# OeShield.net
KiCad netlist of a schematic drawn in EAGLE
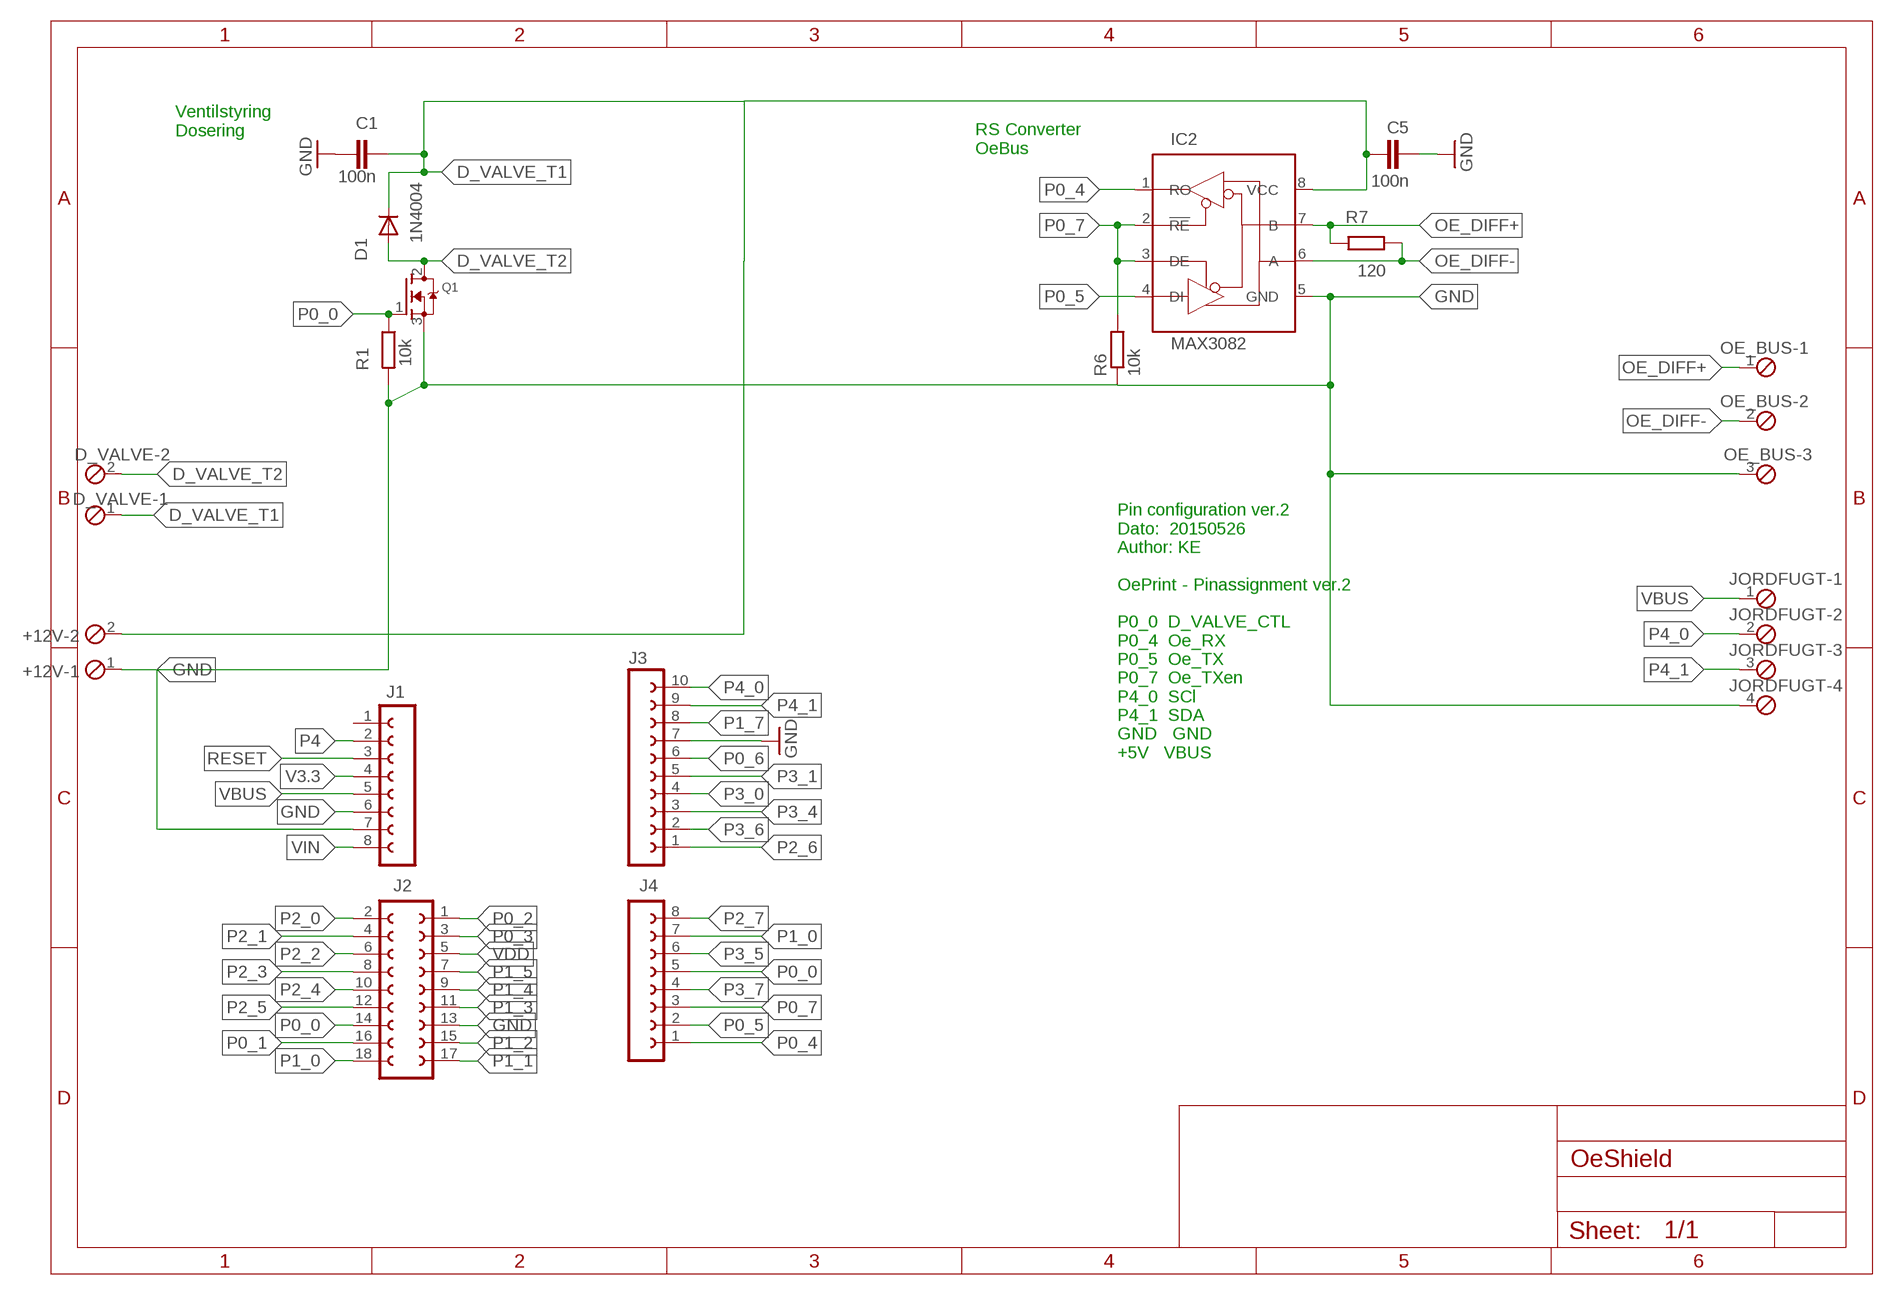
[diagram p0: schematic, sheet 1]

(export (version "E")
  (design (tool "Eeschema 10.0.6"))
  (components
    (comp (ref "+12V")
      (value "MPT2")
      (footprint "eagle-import:2POL254")
      (libsource (lib "eagle-import") (part "MPT2"))
    )
    (comp (ref "C1")
      (value "100n")
      (footprint "eagle-import:C5B3")
      (libsource (lib "eagle-import") (part "C5/3"))
    )
    (comp (ref "C5")
      (value "100n")
      (footprint "eagle-import:C5B3")
      (libsource (lib "eagle-import") (part "C5/3"))
    )
    (comp (ref "D1")
      (value "1N4004")
      (footprint "eagle-import:DO41-10")
      (libsource (lib "eagle-import") (part "1N4004"))
    )
    (comp (ref "D_VALVE")
      (value "MPT2")
      (footprint "eagle-import:2POL254")
      (libsource (lib "eagle-import") (part "MPT2"))
    )
    (comp (ref "IC2")
      (value "MAX3082")
      (footprint "eagle-import:DIL08")
      (libsource (lib "eagle-import") (part "MAX3082CPD"))
    )
    (comp (ref "J1")
      (value "FE08-1")
      (footprint "eagle-import:FE08")
      (libsource (lib "eagle-import") (part "FE08-1"))
    )
    (comp (ref "J2")
      (value "FE09-2")
      (footprint "eagle-import:FE09-2")
      (libsource (lib "eagle-import") (part "FE09-2"))
    )
    (comp (ref "J3")
      (value "FE10-1")
      (footprint "eagle-import:FE10")
      (libsource (lib "eagle-import") (part "FE10-1"))
    )
    (comp (ref "J4")
      (value "FE08-1")
      (footprint "eagle-import:FE08")
      (libsource (lib "eagle-import") (part "FE08-1"))
    )
    (comp (ref "JORDFUGT")
      (value "MPT4")
      (footprint "eagle-import:4POL254")
      (libsource (lib "eagle-import") (part "MPT4"))
    )
    (comp (ref "OE_BUS")
      (value "MPT3")
      (footprint "eagle-import:3POL254")
      (libsource (lib "eagle-import") (part "MPT3"))
    )
    (comp (ref "Q1")
      (value "MOSFET-NGDS_TO220V")
      (footprint "eagle-import:TO220V")
      (libsource (lib "eagle-import") (part "MOSFET-NGDS_TO220V"))
    )
    (comp (ref "R1")
      (value "10k")
      (footprint "eagle-import:0207_12")
      (libsource (lib "eagle-import") (part "R-EU_0207/12"))
    )
    (comp (ref "R6")
      (value "10k")
      (footprint "eagle-import:0207_12")
      (libsource (lib "eagle-import") (part "R-EU_0207/12"))
    )
    (comp (ref "R7")
      (value "120")
      (footprint "eagle-import:0207_12")
      (libsource (lib "eagle-import") (part "R-EU_0207/12"))
    )
  )
  (nets
    (net (code "1") (name "D_VALVE_T1") (class "Default")
      (node (ref "+12V") (pin "2") (pinfunction "1_2") (pintype "passive"))
      (node (ref "C1") (pin "1") (pinfunction "1_1") (pintype "passive"))
      (node (ref "C5") (pin "1") (pinfunction "1_1") (pintype "passive"))
      (node (ref "D1") (pin "C") (pinfunction "C_C") (pintype "passive"))
      (node (ref "D_VALVE") (pin "1") (pinfunction "1_1") (pintype "passive"))
      (node (ref "IC2") (pin "8") (pinfunction "VCC_8") (pintype "output"))
    )
    (net (code "2") (name "D_VALVE_T2") (class "Default")
      (node (ref "D1") (pin "A") (pinfunction "A_A") (pintype "passive"))
      (node (ref "D_VALVE") (pin "2") (pinfunction "1_2") (pintype "passive"))
      (node (ref "Q1") (pin "2") (pinfunction "D_2") (pintype "bidirectional"))
    )
    (net (code "3") (name "GND") (class "Default")
      (node (ref "+12V") (pin "1") (pinfunction "1_1") (pintype "passive"))
      (node (ref "C1") (pin "2") (pinfunction "2_2") (pintype "passive"))
      (node (ref "C5") (pin "2") (pinfunction "2_2") (pintype "passive"))
      (node (ref "IC2") (pin "5") (pinfunction "GND_5") (pintype "input"))
      (node (ref "J1") (pin "6") (pinfunction "6_6") (pintype "passive"))
      (node (ref "J1") (pin "7") (pinfunction "7_7") (pintype "passive"))
      (node (ref "J2") (pin "13") (pinfunction "13_13") (pintype "passive"))
      (node (ref "J3") (pin "7") (pinfunction "7_7") (pintype "passive"))
      (node (ref "JORDFUGT") (pin "4") (pinfunction "1_4") (pintype "passive"))
      (node (ref "OE_BUS") (pin "3") (pinfunction "1_3") (pintype "passive"))
      (node (ref "Q1") (pin "3") (pinfunction "S_3") (pintype "bidirectional"))
      (node (ref "R1") (pin "2") (pinfunction "2_2") (pintype "passive"))
      (node (ref "R6") (pin "1") (pinfunction "1_1") (pintype "passive"))
    )
    (net (code "4") (name "OE_DIFF+") (class "Default")
      (node (ref "IC2") (pin "7") (pinfunction "B_7") (pintype "output"))
      (node (ref "OE_BUS") (pin "1") (pinfunction "1_1") (pintype "passive"))
      (node (ref "R7") (pin "2") (pinfunction "2_2") (pintype "passive"))
    )
    (net (code "5") (name "OE_DIFF-") (class "Default")
      (node (ref "IC2") (pin "6") (pinfunction "A_6") (pintype "input"))
      (node (ref "OE_BUS") (pin "2") (pinfunction "1_2") (pintype "passive"))
      (node (ref "R7") (pin "1") (pinfunction "1_1") (pintype "passive"))
    )
    (net (code "6") (name "P0_0") (class "Default")
      (node (ref "J2") (pin "14") (pinfunction "14_14") (pintype "passive"))
      (node (ref "J4") (pin "5") (pinfunction "5_5") (pintype "passive"))
      (node (ref "Q1") (pin "1") (pinfunction "G_1") (pintype "bidirectional"))
      (node (ref "R1") (pin "1") (pinfunction "1_1") (pintype "passive"))
    )
    (net (code "7") (name "P0_1") (class "Default")
      (node (ref "J2") (pin "16") (pinfunction "16_16") (pintype "passive"))
    )
    (net (code "8") (name "P0_2") (class "Default")
      (node (ref "J2") (pin "1") (pinfunction "1_1") (pintype "passive"))
    )
    (net (code "9") (name "P0_3") (class "Default")
      (node (ref "J2") (pin "3") (pinfunction "3_3") (pintype "passive"))
    )
    (net (code "10") (name "P0_4") (class "Default")
      (node (ref "IC2") (pin "1") (pinfunction "RO_1") (pintype "output"))
      (node (ref "J4") (pin "1") (pinfunction "1_1") (pintype "passive"))
    )
    (net (code "11") (name "P0_5") (class "Default")
      (node (ref "IC2") (pin "4") (pinfunction "DI_4") (pintype "input"))
      (node (ref "J4") (pin "2") (pinfunction "2_2") (pintype "passive"))
    )
    (net (code "12") (name "P0_6") (class "Default")
      (node (ref "J3") (pin "6") (pinfunction "6_6") (pintype "passive"))
    )
    (net (code "13") (name "P0_7") (class "Default")
      (node (ref "IC2") (pin "2") (pinfunction "~{RE}_2") (pintype "input"))
      (node (ref "IC2") (pin "3") (pinfunction "DE_3") (pintype "input"))
      (node (ref "J4") (pin "3") (pinfunction "3_3") (pintype "passive"))
      (node (ref "R6") (pin "2") (pinfunction "2_2") (pintype "passive"))
    )
    (net (code "14") (name "P1_0") (class "Default")
      (node (ref "J2") (pin "18") (pinfunction "18_18") (pintype "passive"))
      (node (ref "J4") (pin "7") (pinfunction "7_7") (pintype "passive"))
    )
    (net (code "15") (name "P1_1") (class "Default")
      (node (ref "J2") (pin "17") (pinfunction "17_17") (pintype "passive"))
    )
    (net (code "16") (name "P1_2") (class "Default")
      (node (ref "J2") (pin "15") (pinfunction "15_15") (pintype "passive"))
    )
    (net (code "17") (name "P1_3") (class "Default")
      (node (ref "J2") (pin "11") (pinfunction "11_11") (pintype "passive"))
    )
    (net (code "18") (name "P1_4") (class "Default")
      (node (ref "J2") (pin "9") (pinfunction "9_9") (pintype "passive"))
    )
    (net (code "19") (name "P1_5") (class "Default")
      (node (ref "J2") (pin "7") (pinfunction "7_7") (pintype "passive"))
    )
    (net (code "20") (name "P1_7") (class "Default")
      (node (ref "J3") (pin "8") (pinfunction "8_8") (pintype "passive"))
    )
    (net (code "21") (name "P2_0") (class "Default")
      (node (ref "J2") (pin "2") (pinfunction "2_2") (pintype "passive"))
    )
    (net (code "22") (name "P2_1") (class "Default")
      (node (ref "J2") (pin "4") (pinfunction "4_4") (pintype "passive"))
    )
    (net (code "23") (name "P2_2") (class "Default")
      (node (ref "J2") (pin "6") (pinfunction "6_6") (pintype "passive"))
    )
    (net (code "24") (name "P2_3") (class "Default")
      (node (ref "J2") (pin "8") (pinfunction "8_8") (pintype "passive"))
    )
    (net (code "25") (name "P2_4") (class "Default")
      (node (ref "J2") (pin "10") (pinfunction "10_10") (pintype "passive"))
    )
    (net (code "26") (name "P2_5") (class "Default")
      (node (ref "J2") (pin "12") (pinfunction "12_12") (pintype "passive"))
    )
    (net (code "27") (name "P2_6") (class "Default")
      (node (ref "J3") (pin "1") (pinfunction "1_1") (pintype "passive"))
    )
    (net (code "28") (name "P2_7") (class "Default")
      (node (ref "J4") (pin "8") (pinfunction "8_8") (pintype "passive"))
    )
    (net (code "29") (name "P3_0") (class "Default")
      (node (ref "J3") (pin "4") (pinfunction "4_4") (pintype "passive"))
    )
    (net (code "30") (name "P3_1") (class "Default")
      (node (ref "J3") (pin "5") (pinfunction "5_5") (pintype "passive"))
    )
    (net (code "31") (name "P3_4") (class "Default")
      (node (ref "J3") (pin "3") (pinfunction "3_3") (pintype "passive"))
    )
    (net (code "32") (name "P3_5") (class "Default")
      (node (ref "J4") (pin "6") (pinfunction "6_6") (pintype "passive"))
    )
    (net (code "33") (name "P3_6") (class "Default")
      (node (ref "J3") (pin "2") (pinfunction "2_2") (pintype "passive"))
    )
    (net (code "34") (name "P3_7") (class "Default")
      (node (ref "J4") (pin "4") (pinfunction "4_4") (pintype "passive"))
    )
    (net (code "35") (name "P4") (class "Default")
      (node (ref "J1") (pin "2") (pinfunction "2_2") (pintype "passive"))
    )
    (net (code "36") (name "P4_0") (class "Default")
      (node (ref "J3") (pin "10") (pinfunction "10_10") (pintype "passive"))
      (node (ref "JORDFUGT") (pin "2") (pinfunction "1_2") (pintype "passive"))
    )
    (net (code "37") (name "P4_1") (class "Default")
      (node (ref "J3") (pin "9") (pinfunction "9_9") (pintype "passive"))
      (node (ref "JORDFUGT") (pin "3") (pinfunction "1_3") (pintype "passive"))
    )
    (net (code "38") (name "RESET") (class "Default")
      (node (ref "J1") (pin "3") (pinfunction "3_3") (pintype "passive"))
    )
    (net (code "39") (name "V3.3") (class "Default")
      (node (ref "J1") (pin "4") (pinfunction "4_4") (pintype "passive"))
    )
    (net (code "40") (name "VBUS") (class "Default")
      (node (ref "J1") (pin "5") (pinfunction "5_5") (pintype "passive"))
      (node (ref "JORDFUGT") (pin "1") (pinfunction "1_1") (pintype "passive"))
    )
    (net (code "41") (name "VDD") (class "Default")
      (node (ref "J2") (pin "5") (pinfunction "5_5") (pintype "passive"))
    )
    (net (code "42") (name "VIN") (class "Default")
      (node (ref "J1") (pin "8") (pinfunction "8_8") (pintype "passive"))
    )
    (net (code "43") (name "unconnected-(J1-Pad1)") (class "Default")
      (node (ref "J1") (pin "1") (pinfunction "1_1") (pintype "passive"))
    )
  )
)
